# laundrysensor.net
KiCad netlist of a schematic drawn in EAGLE
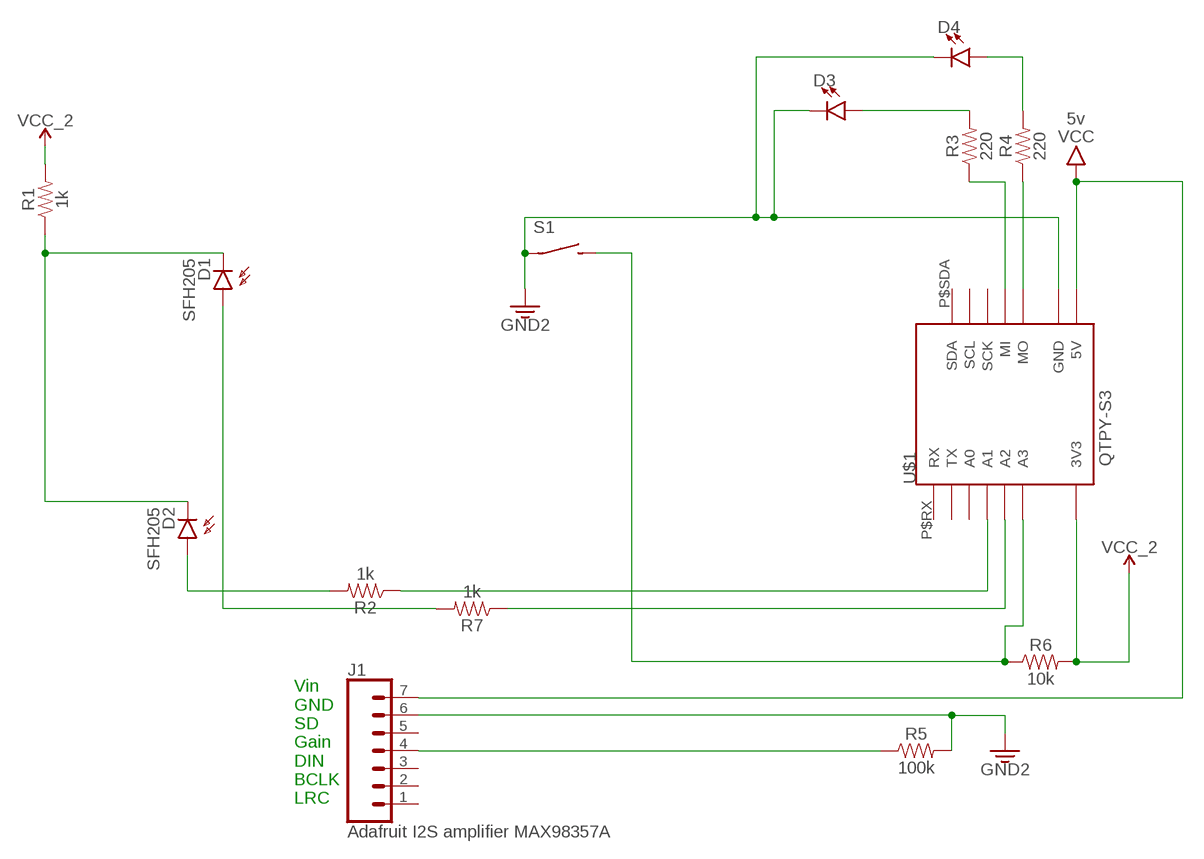
[diagram p0: schematic, sheet 1]

(export (version "E")
  (design (tool "Eeschema 10.0.6"))
  (components
    (comp (ref "D1")
      (value "SFH205")
      (footprint "eagle-import:SFH205")
      (libsource (lib "eagle-import") (part "SFH205"))
    )
    (comp (ref "D2")
      (value "SFH205")
      (footprint "eagle-import:SFH205")
      (libsource (lib "eagle-import") (part "SFH205"))
    )
    (comp (ref "D3")
      (value "LED3MM")
      (footprint "eagle-import:LED_3MM")
      (libsource (lib "eagle-import") (part "LED3MM"))
    )
    (comp (ref "D4")
      (value "LED3MM")
      (footprint "eagle-import:LED_3MM")
      (libsource (lib "eagle-import") (part "LED3MM"))
    )
    (comp (ref "J1")
      (value "Adafruit I2S amplifier MAX98357A")
      (footprint "eagle-import:1X07")
      (libsource (lib "eagle-import") (part "CONN_07"))
    )
    (comp (ref "R1")
      (value "1k")
      (footprint "eagle-import:AXIAL-0.3")
      (libsource (lib "eagle-import") (part "1KOHM-HORIZ-1/4W-5%"))
    )
    (comp (ref "R2")
      (value "1k")
      (footprint "eagle-import:AXIAL-0.3")
      (libsource (lib "eagle-import") (part "1KOHM-HORIZ-1/4W-5%"))
    )
    (comp (ref "R3")
      (value "220")
      (footprint "eagle-import:AXIAL-0.3")
      (libsource (lib "eagle-import") (part "1KOHM-HORIZ-1/4W-5%"))
    )
    (comp (ref "R4")
      (value "220")
      (footprint "eagle-import:AXIAL-0.3")
      (libsource (lib "eagle-import") (part "1KOHM-HORIZ-1/4W-5%"))
    )
    (comp (ref "R5")
      (value "100k")
      (footprint "eagle-import:AXIAL-0.3")
      (libsource (lib "eagle-import") (part "100KOHM-HORIZ-1/4W-1%"))
    )
    (comp (ref "R6")
      (value "10k")
      (footprint "eagle-import:AXIAL-0.3")
      (libsource (lib "eagle-import") (part "10KOHM-HORIZ-1/4W-1%"))
    )
    (comp (ref "R7")
      (value "1k")
      (footprint "eagle-import:AXIAL-0.3")
      (libsource (lib "eagle-import") (part "1KOHM-HORIZ-1/4W-5%"))
    )
    (comp (ref "S1")
      (value "SPST_OFFBOARD_LG")
      (footprint "eagle-import:OFFBOARD_2_LG")
      (libsource (lib "eagle-import") (part "SPST_OFFBOARD_LG"))
    )
    (comp (ref "U$1")
      (value "QTPY-S3")
      (footprint "eagle-import:QTPY-S3")
      (libsource (lib "eagle-import") (part "QTPY-S3"))
    )
  )
  (nets
    (net (code "1") (name "5v") (class "Default")
      (node (ref "J1") (pin "7") (pinfunction "7_7") (pintype "passive"))
      (node (ref "U$1") (pin "P$5V") (pinfunction "5V_P$5V") (pintype "power_in"))
    )
    (net (code "2") (name "GND2") (class "Default")
      (node (ref "D3") (pin "K") (pinfunction "C_K") (pintype "passive"))
      (node (ref "D4") (pin "K") (pinfunction "C_K") (pintype "passive"))
      (node (ref "J1") (pin "6") (pinfunction "6_6") (pintype "passive"))
      (node (ref "R5") (pin "P$2") (pinfunction "2_P$2") (pintype "passive"))
      (node (ref "S1") (pin "P$1") (pinfunction "P_P$1") (pintype "passive"))
      (node (ref "U$1") (pin "P$GND") (pinfunction "GND_P$GND") (pintype "power_in"))
    )
    (net (code "3") (name "Net-(D1-C)") (class "Default")
      (node (ref "D1") (pin "K") (pinfunction "C_K") (pintype "passive"))
      (node (ref "D2") (pin "K") (pinfunction "C_K") (pintype "passive"))
      (node (ref "R1") (pin "P$1") (pinfunction "1_P$1") (pintype "passive"))
    )
    (net (code "4") (name "Net-(R2-1)") (class "Default")
      (node (ref "R2") (pin "P$1") (pinfunction "1_P$1") (pintype "passive"))
      (node (ref "U$1") (pin "P$A1") (pinfunction "A1_P$A1") (pintype "bidirectional"))
    )
    (net (code "5") (name "Net-(R2-2)") (class "Default")
      (node (ref "D2") (pin "A") (pinfunction "A_A") (pintype "passive"))
      (node (ref "R2") (pin "P$2") (pinfunction "2_P$2") (pintype "passive"))
    )
    (net (code "6") (name "Net-(R3-1)") (class "Default")
      (node (ref "R3") (pin "P$1") (pinfunction "1_P$1") (pintype "passive"))
      (node (ref "U$1") (pin "P$MI") (pinfunction "MI_P$MI") (pintype "bidirectional"))
    )
    (net (code "7") (name "Net-(R3-2)") (class "Default")
      (node (ref "D3") (pin "A") (pinfunction "A_A") (pintype "passive"))
      (node (ref "R3") (pin "P$2") (pinfunction "2_P$2") (pintype "passive"))
    )
    (net (code "8") (name "Net-(R4-1)") (class "Default")
      (node (ref "R4") (pin "P$1") (pinfunction "1_P$1") (pintype "passive"))
      (node (ref "U$1") (pin "P$MO") (pinfunction "MO_P$MO") (pintype "bidirectional"))
    )
    (net (code "9") (name "Net-(R4-2)") (class "Default")
      (node (ref "D4") (pin "A") (pinfunction "A_A") (pintype "passive"))
      (node (ref "R4") (pin "P$2") (pinfunction "2_P$2") (pintype "passive"))
    )
    (net (code "10") (name "Net-(R5-1)") (class "Default")
      (node (ref "J1") (pin "4") (pinfunction "4_4") (pintype "passive"))
      (node (ref "R5") (pin "P$1") (pinfunction "1_P$1") (pintype "passive"))
    )
    (net (code "11") (name "Net-(R6-1)") (class "Default")
      (node (ref "R6") (pin "P$1") (pinfunction "1_P$1") (pintype "passive"))
      (node (ref "S1") (pin "P$2") (pinfunction "S_P$2") (pintype "passive"))
      (node (ref "U$1") (pin "P$A3") (pinfunction "A3_P$A3") (pintype "bidirectional"))
    )
    (net (code "12") (name "Net-(R7-1)") (class "Default")
      (node (ref "R7") (pin "P$1") (pinfunction "1_P$1") (pintype "passive"))
      (node (ref "U$1") (pin "P$A2") (pinfunction "A2_P$A2") (pintype "bidirectional"))
    )
    (net (code "13") (name "Net-(R7-2)") (class "Default")
      (node (ref "D1") (pin "A") (pinfunction "A_A") (pintype "passive"))
      (node (ref "R7") (pin "P$2") (pinfunction "2_P$2") (pintype "passive"))
    )
    (net (code "14") (name "VCC_2") (class "Default")
      (node (ref "R1") (pin "P$2") (pinfunction "2_P$2") (pintype "passive"))
      (node (ref "R6") (pin "P$2") (pinfunction "2_P$2") (pintype "passive"))
      (node (ref "U$1") (pin "P$3V") (pinfunction "3V3_P$3V") (pintype "power_in"))
    )
    (net (code "15") (name "unconnected-(J1-Pad1)") (class "Default")
      (node (ref "J1") (pin "1") (pinfunction "1_1") (pintype "passive"))
    )
    (net (code "16") (name "unconnected-(J1-Pad2)") (class "Default")
      (node (ref "J1") (pin "2") (pinfunction "2_2") (pintype "passive"))
    )
    (net (code "17") (name "unconnected-(J1-Pad3)") (class "Default")
      (node (ref "J1") (pin "3") (pinfunction "3_3") (pintype "passive"))
    )
    (net (code "18") (name "unconnected-(J1-Pad5)") (class "Default")
      (node (ref "J1") (pin "5") (pinfunction "5_5") (pintype "passive"))
    )
    (net (code "19") (name "unconnected-(U$1-A0-PadP$A0)") (class "Default")
      (node (ref "U$1") (pin "P$A0") (pinfunction "A0_P$A0") (pintype "bidirectional"))
    )
    (net (code "20") (name "unconnected-(U$1-RX-PadP$RX)") (class "Default")
      (node (ref "U$1") (pin "P$RX") (pinfunction "RX_P$RX") (pintype "bidirectional"))
    )
    (net (code "21") (name "unconnected-(U$1-SCK-PadP$SCK)") (class "Default")
      (node (ref "U$1") (pin "P$SCK") (pinfunction "SCK_P$SCK") (pintype "bidirectional"))
    )
    (net (code "22") (name "unconnected-(U$1-SCL-PadP$SCL)") (class "Default")
      (node (ref "U$1") (pin "P$SCL") (pinfunction "SCL_P$SCL") (pintype "bidirectional"))
    )
    (net (code "23") (name "unconnected-(U$1-SDA-PadP$SDA)") (class "Default")
      (node (ref "U$1") (pin "P$SDA") (pinfunction "SDA_P$SDA") (pintype "bidirectional"))
    )
    (net (code "24") (name "unconnected-(U$1-TX-PadP$TX)") (class "Default")
      (node (ref "U$1") (pin "P$TX") (pinfunction "TX_P$TX") (pintype "bidirectional"))
    )
  )
)
